# DRIVERS_CONNECTORS.net
KiCad netlist of a schematic drawn in Altium Designer
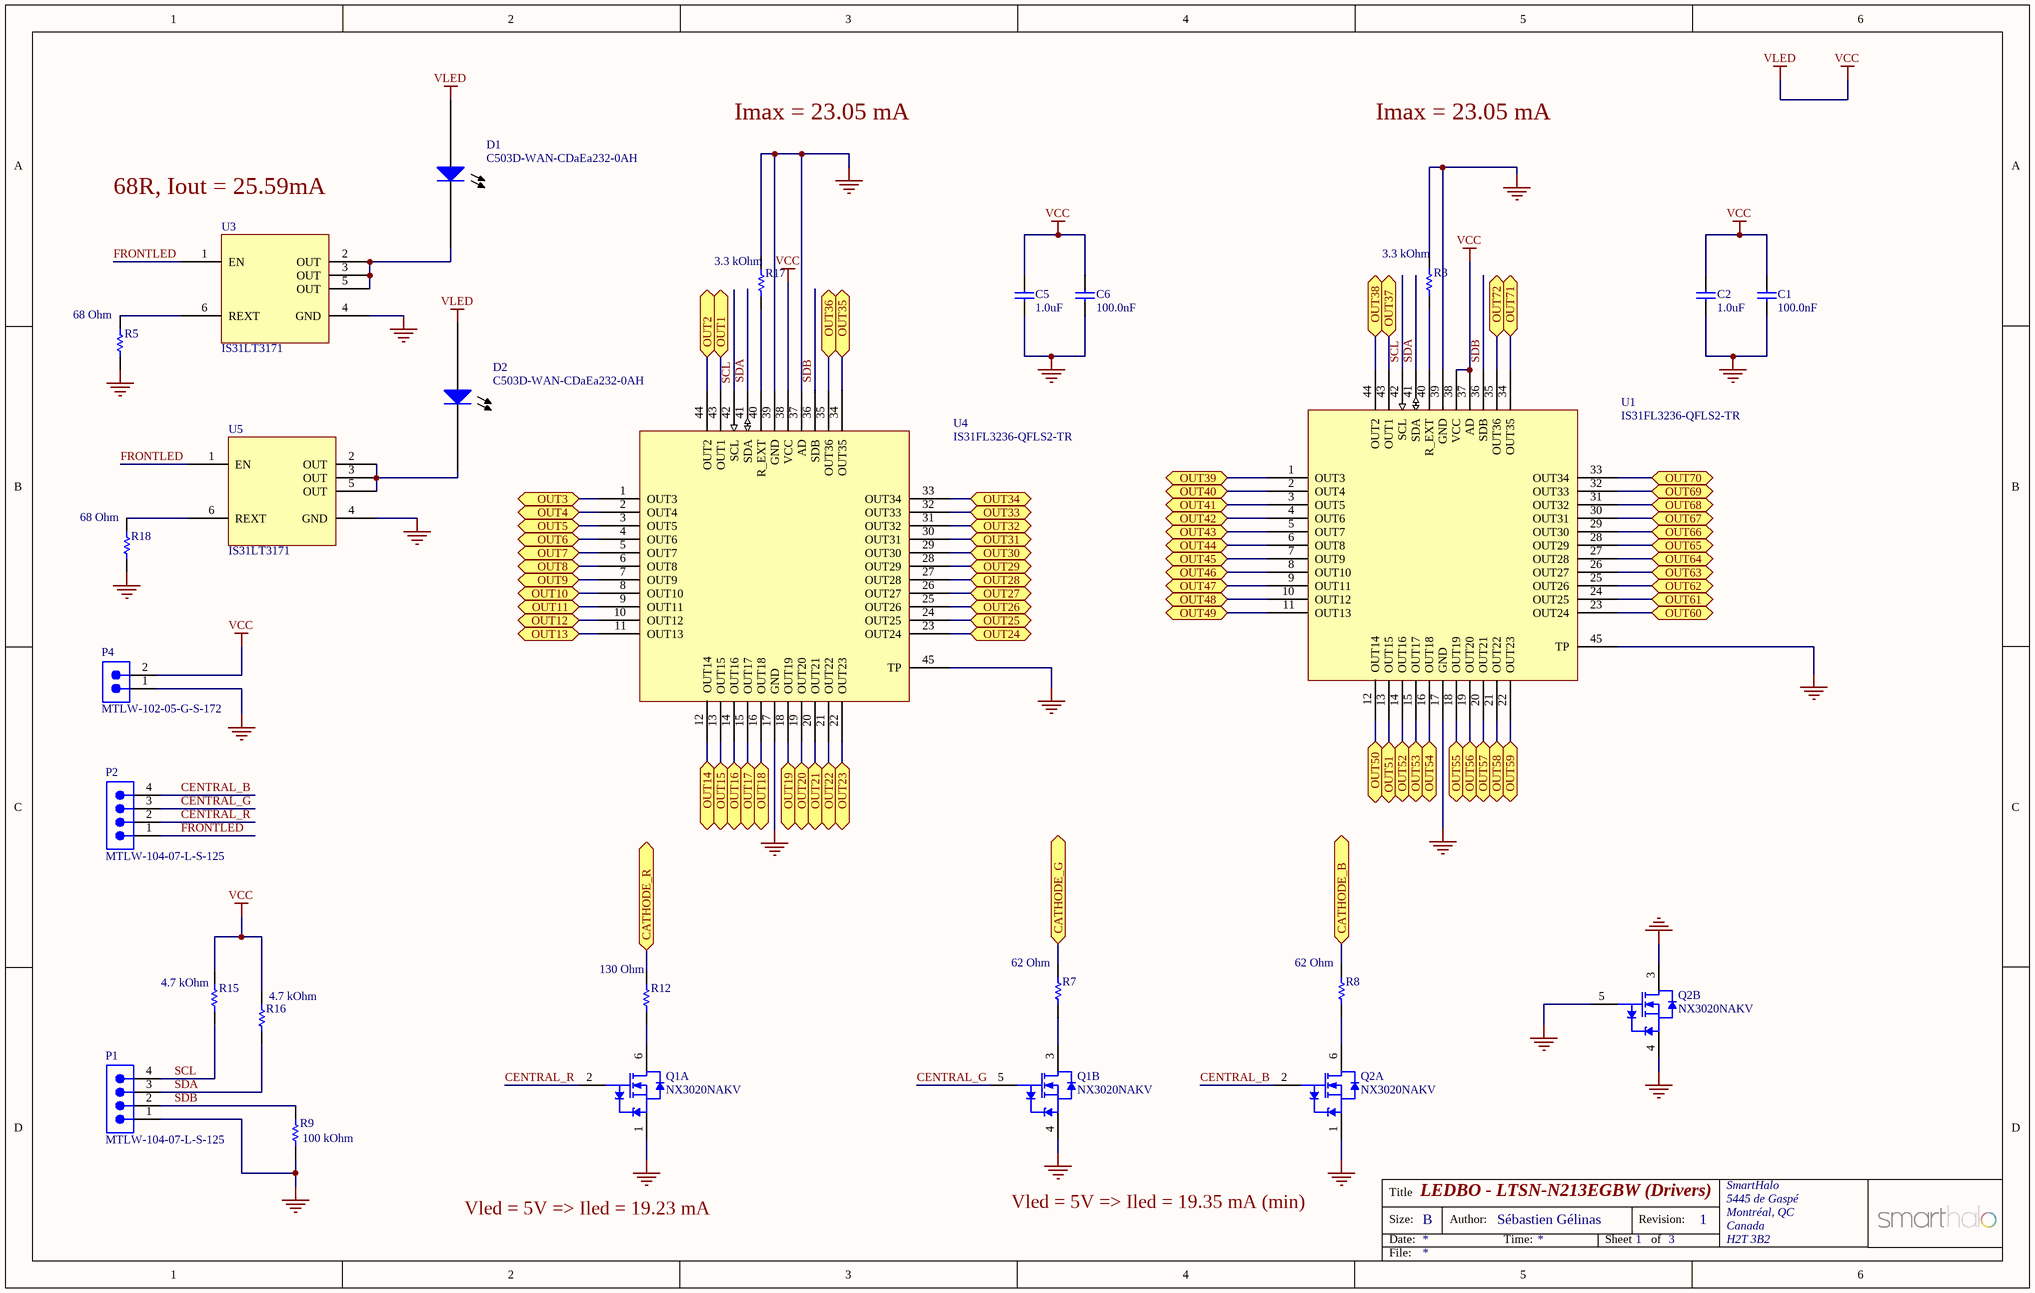
[diagram p0: DRIVERS_CONNECTORS.SchDoc]

(export (version "E")
  (design (tool "Eeschema 10.0.6"))
  (components
    (comp (ref "C1")
      (value "100.0nF")
      (footprint "CAPC0603(1608)100_N")
      (description "Chip Cap 0603 X7R 10%")
      (fields (field (name "PART NUMBER") "C0402-1n0") (field (name "PUBLISHER") "Nordic Semiconductor"))
      (libsource (lib "SmartHalo") (part "CAP0603"))
    )
    (comp (ref "C2")
      (value "1.0uF")
      (footprint "CAPC0603(1608)100_N")
      (description "Chip Cap 0603 X7R 10%")
      (fields (field (name "PART NUMBER") "C0402-1n0") (field (name "PUBLISHER") "Nordic Semiconductor"))
      (libsource (lib "SmartHalo") (part "CAP0603"))
    )
    (comp (ref "C5")
      (value "1.0uF")
      (footprint "CAPC0603(1608)100_N")
      (description "Chip Cap 0603 X7R 10%")
      (fields (field (name "PART NUMBER") "C0402-1n0") (field (name "PUBLISHER") "Nordic Semiconductor"))
      (libsource (lib "SmartHalo") (part "CAP0603"))
    )
    (comp (ref "C6")
      (value "100.0nF")
      (footprint "CAPC0603(1608)100_N")
      (description "Chip Cap 0603 X7R 10%")
      (fields (field (name "PART NUMBER") "C0402-1n0") (field (name "PUBLISHER") "Nordic Semiconductor"))
      (libsource (lib "SmartHalo") (part "CAP0603"))
    )
    (comp (ref "D1")
      (value "C503D-WAN-CDaEa232-0AH")
      (footprint "FRONTLED_PADS")
      (description "Cree 5mm Round LED C503D-WAN-CDaEa232-0AH")
      (fields (field (name "MANUFACTURER") "Cree"))
      (libsource (lib "SmartHalo") (part "C503D-WAN-CDaEa232-0AH"))
    )
    (comp (ref "D2")
      (value "C503D-WAN-CDaEa232-0AH")
      (footprint "FRONTLED_PADS")
      (description "Cree 5mm Round LED C503D-WAN-CDaEa232-0AH")
      (fields (field (name "MANUFACTURER") "Cree"))
      (libsource (lib "SmartHalo") (part "C503D-WAN-CDaEa232-0AH"))
    )
    (comp (ref "P1")
      (value "MTLW-104-07-L-S-125")
      (footprint "SMTC-MTLW-104-07-X-S-125")
      (fields (field (name "MANUFACTURER") "Samtec"))
      (libsource (lib "SmartHalo") (part "SMTC-MTLW-104-07-X-S-125"))
    )
    (comp (ref "P2")
      (value "MTLW-104-07-L-S-125")
      (footprint "SMTC-MTLW-104-07-X-S-125")
      (fields (field (name "MANUFACTURER") "Samtec"))
      (libsource (lib "SmartHalo") (part "SMTC-MTLW-104-07-X-S-125"))
    )
    (comp (ref "P4")
      (value "MTLW-102-05-G-S-172")
      (footprint "SMTC-MTLW-102-05-X-S-172")
      (fields (field (name "MANUFACTURER") "Samtec"))
      (libsource (lib "SmartHalo") (part "SMTC-MTLW-102-05-X-S-172"))
    )
    (comp (ref "Q1")
      (value "NX3020NAKV")
      (footprint "SOT666")
      (description "30 V, 200 mA dual N-channel Trench MOSFET")
      (fields (field (name "MANUFACTURER") "NXP Semiconductors"))
      (libsource (lib "SmartHalo") (part "NX3020NAKV"))
    )
    (comp (ref "Q2")
      (value "NX3020NAKV")
      (footprint "SOT666")
      (description "30 V, 200 mA dual N-channel Trench MOSFET")
      (fields (field (name "MANUFACTURER") "NXP Semiconductors"))
      (libsource (lib "SmartHalo") (part "NX3020NAKV"))
    )
    (comp (ref "R3")
      (value "3.3 kOhm")
      (footprint "RESC0603(1608)_M")
      (description "3K3 0.1W 5% 0603 (1608 Metric)  SMD")
      (fields (field (name "TOLERANCE") "5 %") (field (name "POWER") "0.1 W"))
      (libsource (lib "SmartHalo") (part "CMP-1012-00090-1"))
    )
    (comp (ref "R5")
      (value "68 Ohm")
      (footprint "RESC0603(1608)_M")
      (description "68R 0.1W 5% 0603 (1608 Metric)  SMD")
      (fields (field (name "TOLERANCE") "5 %") (field (name "POWER") "0.1 W"))
      (libsource (lib "SmartHalo") (part "CMP-1012-00090-1"))
    )
    (comp (ref "R7")
      (value "62 Ohm")
      (footprint "RESC0603(1608)_M")
      (description "62R 0.1W 5% 0603 (1608 Metric)  SMD")
      (fields (field (name "TOLERANCE") "5 %") (field (name "POWER") "0.1 W"))
      (libsource (lib "SmartHalo") (part "CMP-1012-00090-1"))
    )
    (comp (ref "R8")
      (value "62 Ohm")
      (footprint "RESC0603(1608)_M")
      (description "62R 0.1W 5% 0603 (1608 Metric)  SMD")
      (fields (field (name "TOLERANCE") "5 %") (field (name "POWER") "0.1 W"))
      (libsource (lib "SmartHalo") (part "CMP-1012-00090-1"))
    )
    (comp (ref "R9")
      (value "100 kOhm")
      (footprint "RESC0603(1608)_M")
      (description "100k 0.1W 5% 0603 (1608 Metric)  SMD")
      (fields (field (name "TOLERANCE") "5 %") (field (name "POWER") "0.1 W"))
      (libsource (lib "SmartHalo") (part "CMP-1012-00090-1"))
    )
    (comp (ref "R12")
      (value "130 Ohm")
      (footprint "RESC0603(1608)_M")
      (description "130R 0.1W 5% 0603 (1608 Metric)  SMD")
      (fields (field (name "TOLERANCE") "5 %") (field (name "POWER") "0.1 W"))
      (libsource (lib "SmartHalo") (part "CMP-1012-00090-1"))
    )
    (comp (ref "R15")
      (value "4.7 kOhm")
      (footprint "RESC0603(1608)_M")
      (description "4K7 0.1W 5% 0603 (1608 Metric)  SMD")
      (fields (field (name "TOLERANCE") "5 %") (field (name "POWER") "0.1 W"))
      (libsource (lib "SmartHalo") (part "CMP-1012-00090-1"))
    )
    (comp (ref "R16")
      (value "4.7 kOhm")
      (footprint "RESC0603(1608)_M")
      (description "4K7 0.1W 5% 0603 (1608 Metric)  SMD")
      (fields (field (name "TOLERANCE") "5 %") (field (name "POWER") "0.1 W"))
      (libsource (lib "SmartHalo") (part "CMP-1012-00090-1"))
    )
    (comp (ref "R17")
      (value "3.3 kOhm")
      (footprint "RESC0603(1608)_M")
      (description "3K3 0.1W 5% 0603 (1608 Metric)  SMD")
      (fields (field (name "TOLERANCE") "5 %") (field (name "POWER") "0.1 W"))
      (libsource (lib "SmartHalo") (part "CMP-1012-00090-1"))
    )
    (comp (ref "R18")
      (value "68 Ohm")
      (footprint "RESC0603(1608)_M")
      (description "68R 0.1W 5% 0603 (1608 Metric)  SMD")
      (fields (field (name "TOLERANCE") "5 %") (field (name "POWER") "0.1 W"))
      (libsource (lib "SmartHalo") (part "CMP-1012-00090-1"))
    )
    (comp (ref "U1")
      (value "IS31FL3236-QFLS2-TR")
      (footprint "QFN-44")
      (description "IC 36 CHANNELS LED DRIVER")
      (fields (field (name "MANUFACTURER") "ISSI"))
      (libsource (lib "SmartHalo") (part "IS31FL3236-QFLS2-TR"))
    )
    (comp (ref "U3")
      (value "IS31LT3171")
      (footprint "SOT23-6")
      (description "10-TO-150MA CONSTANT-CURRENT LED DRIVER")
      (libsource (lib "SmartHalo") (part "IS31LT3171"))
    )
    (comp (ref "U4")
      (value "IS31FL3236-QFLS2-TR")
      (footprint "QFN-44")
      (description "IC 36 CHANNELS LED DRIVER")
      (fields (field (name "MANUFACTURER") "ISSI"))
      (libsource (lib "SmartHalo") (part "IS31FL3236-QFLS2-TR"))
    )
    (comp (ref "U5")
      (value "IS31LT3171")
      (footprint "SOT23-6")
      (description "10-TO-150MA CONSTANT-CURRENT LED DRIVER")
      (libsource (lib "SmartHalo") (part "IS31LT3171"))
    )
  )
  (nets
    (net (code "1") (name "/CATHODE_B") (class "Default")
      (node (ref "R8") (pin "2") (pinfunction "2_2") (pintype "passive"))
    )
    (net (code "2") (name "/CATHODE_G") (class "Default")
      (node (ref "R7") (pin "2") (pinfunction "2_2") (pintype "passive"))
    )
    (net (code "3") (name "/CATHODE_R") (class "Default")
      (node (ref "R12") (pin "2") (pinfunction "2_2") (pintype "passive"))
    )
    (net (code "4") (name "/CENTRAL_B") (class "Default")
      (node (ref "P2") (pin "4") (pinfunction "4_4") (pintype "passive"))
      (node (ref "Q2") (pin "2") (pinfunction "G1_2") (pintype "passive"))
    )
    (net (code "5") (name "/CENTRAL_G") (class "Default")
      (node (ref "P2") (pin "3") (pinfunction "3_3") (pintype "passive"))
      (node (ref "Q1") (pin "5") (pinfunction "G2_5") (pintype "passive"))
    )
    (net (code "6") (name "/CENTRAL_R") (class "Default")
      (node (ref "P2") (pin "2") (pinfunction "2_2") (pintype "passive"))
      (node (ref "Q1") (pin "2") (pinfunction "G1_2") (pintype "passive"))
    )
    (net (code "7") (name "/FRONTLED") (class "Default")
      (node (ref "P2") (pin "1") (pinfunction "1_1") (pintype "passive"))
      (node (ref "U3") (pin "1") (pinfunction "EN_1") (pintype "passive"))
      (node (ref "U5") (pin "1") (pinfunction "EN_1") (pintype "passive"))
    )
    (net (code "8") (name "/OUT1") (class "Default")
      (node (ref "U4") (pin "43") (pinfunction "OUT1_43") (pintype "passive"))
    )
    (net (code "9") (name "/OUT2") (class "Default")
      (node (ref "U4") (pin "44") (pinfunction "OUT2_44") (pintype "passive"))
    )
    (net (code "10") (name "/OUT3") (class "Default")
      (node (ref "U4") (pin "1") (pinfunction "OUT3_1") (pintype "passive"))
    )
    (net (code "11") (name "/OUT4") (class "Default")
      (node (ref "U4") (pin "2") (pinfunction "OUT4_2") (pintype "passive"))
    )
    (net (code "12") (name "/OUT5") (class "Default")
      (node (ref "U4") (pin "3") (pinfunction "OUT5_3") (pintype "passive"))
    )
    (net (code "13") (name "/OUT6") (class "Default")
      (node (ref "U4") (pin "4") (pinfunction "OUT6_4") (pintype "passive"))
    )
    (net (code "14") (name "/OUT7") (class "Default")
      (node (ref "U4") (pin "5") (pinfunction "OUT7_5") (pintype "passive"))
    )
    (net (code "15") (name "/OUT8") (class "Default")
      (node (ref "U4") (pin "6") (pinfunction "OUT8_6") (pintype "passive"))
    )
    (net (code "16") (name "/OUT9") (class "Default")
      (node (ref "U4") (pin "7") (pinfunction "OUT9_7") (pintype "passive"))
    )
    (net (code "17") (name "/OUT10") (class "Default")
      (node (ref "U4") (pin "8") (pinfunction "OUT10_8") (pintype "passive"))
    )
    (net (code "18") (name "/OUT11") (class "Default")
      (node (ref "U4") (pin "9") (pinfunction "OUT11_9") (pintype "passive"))
    )
    (net (code "19") (name "/OUT12") (class "Default")
      (node (ref "U4") (pin "10") (pinfunction "OUT12_10") (pintype "passive"))
    )
    (net (code "20") (name "/OUT13") (class "Default")
      (node (ref "U4") (pin "11") (pinfunction "OUT13_11") (pintype "passive"))
    )
    (net (code "21") (name "/OUT14") (class "Default")
      (node (ref "U4") (pin "12") (pinfunction "OUT14_12") (pintype "passive"))
    )
    (net (code "22") (name "/OUT15") (class "Default")
      (node (ref "U4") (pin "13") (pinfunction "OUT15_13") (pintype "passive"))
    )
    (net (code "23") (name "/OUT16") (class "Default")
      (node (ref "U4") (pin "14") (pinfunction "OUT16_14") (pintype "passive"))
    )
    (net (code "24") (name "/OUT17") (class "Default")
      (node (ref "U4") (pin "15") (pinfunction "OUT17_15") (pintype "passive"))
    )
    (net (code "25") (name "/OUT18") (class "Default")
      (node (ref "U4") (pin "16") (pinfunction "OUT18_16") (pintype "passive"))
    )
    (net (code "26") (name "/OUT19") (class "Default")
      (node (ref "U4") (pin "18") (pinfunction "OUT19_18") (pintype "passive"))
    )
    (net (code "27") (name "/OUT20") (class "Default")
      (node (ref "U4") (pin "19") (pinfunction "OUT20_19") (pintype "passive"))
    )
    (net (code "28") (name "/OUT21") (class "Default")
      (node (ref "U4") (pin "20") (pinfunction "OUT21_20") (pintype "passive"))
    )
    (net (code "29") (name "/OUT22") (class "Default")
      (node (ref "U4") (pin "21") (pinfunction "OUT22_21") (pintype "passive"))
    )
    (net (code "30") (name "/OUT23") (class "Default")
      (node (ref "U4") (pin "22") (pinfunction "OUT23_22") (pintype "passive"))
    )
    (net (code "31") (name "/OUT24") (class "Default")
      (node (ref "U4") (pin "23") (pinfunction "OUT24_23") (pintype "passive"))
    )
    (net (code "32") (name "/OUT25") (class "Default")
      (node (ref "U4") (pin "24") (pinfunction "OUT25_24") (pintype "passive"))
    )
    (net (code "33") (name "/OUT26") (class "Default")
      (node (ref "U4") (pin "25") (pinfunction "OUT26_25") (pintype "passive"))
    )
    (net (code "34") (name "/OUT27") (class "Default")
      (node (ref "U4") (pin "26") (pinfunction "OUT27_26") (pintype "passive"))
    )
    (net (code "35") (name "/OUT28") (class "Default")
      (node (ref "U4") (pin "27") (pinfunction "OUT28_27") (pintype "passive"))
    )
    (net (code "36") (name "/OUT29") (class "Default")
      (node (ref "U4") (pin "28") (pinfunction "OUT29_28") (pintype "passive"))
    )
    (net (code "37") (name "/OUT30") (class "Default")
      (node (ref "U4") (pin "29") (pinfunction "OUT30_29") (pintype "passive"))
    )
    (net (code "38") (name "/OUT31") (class "Default")
      (node (ref "U4") (pin "30") (pinfunction "OUT31_30") (pintype "passive"))
    )
    (net (code "39") (name "/OUT32") (class "Default")
      (node (ref "U4") (pin "31") (pinfunction "OUT32_31") (pintype "passive"))
    )
    (net (code "40") (name "/OUT33") (class "Default")
      (node (ref "U4") (pin "32") (pinfunction "OUT33_32") (pintype "passive"))
    )
    (net (code "41") (name "/OUT34") (class "Default")
      (node (ref "U4") (pin "33") (pinfunction "OUT34_33") (pintype "passive"))
    )
    (net (code "42") (name "/OUT35") (class "Default")
      (node (ref "U4") (pin "34") (pinfunction "OUT35_34") (pintype "passive"))
    )
    (net (code "43") (name "/OUT36") (class "Default")
      (node (ref "U4") (pin "35") (pinfunction "OUT36_35") (pintype "passive"))
    )
    (net (code "44") (name "/OUT37") (class "Default")
      (node (ref "U1") (pin "43") (pinfunction "OUT1_43") (pintype "passive"))
    )
    (net (code "45") (name "/OUT38") (class "Default")
      (node (ref "U1") (pin "44") (pinfunction "OUT2_44") (pintype "passive"))
    )
    (net (code "46") (name "/OUT39") (class "Default")
      (node (ref "U1") (pin "1") (pinfunction "OUT3_1") (pintype "passive"))
    )
    (net (code "47") (name "/OUT40") (class "Default")
      (node (ref "U1") (pin "2") (pinfunction "OUT4_2") (pintype "passive"))
    )
    (net (code "48") (name "/OUT41") (class "Default")
      (node (ref "U1") (pin "3") (pinfunction "OUT5_3") (pintype "passive"))
    )
    (net (code "49") (name "/OUT42") (class "Default")
      (node (ref "U1") (pin "4") (pinfunction "OUT6_4") (pintype "passive"))
    )
    (net (code "50") (name "/OUT43") (class "Default")
      (node (ref "U1") (pin "5") (pinfunction "OUT7_5") (pintype "passive"))
    )
    (net (code "51") (name "/OUT44") (class "Default")
      (node (ref "U1") (pin "6") (pinfunction "OUT8_6") (pintype "passive"))
    )
    (net (code "52") (name "/OUT45") (class "Default")
      (node (ref "U1") (pin "7") (pinfunction "OUT9_7") (pintype "passive"))
    )
    (net (code "53") (name "/OUT46") (class "Default")
      (node (ref "U1") (pin "8") (pinfunction "OUT10_8") (pintype "passive"))
    )
    (net (code "54") (name "/OUT47") (class "Default")
      (node (ref "U1") (pin "9") (pinfunction "OUT11_9") (pintype "passive"))
    )
    (net (code "55") (name "/OUT48") (class "Default")
      (node (ref "U1") (pin "10") (pinfunction "OUT12_10") (pintype "passive"))
    )
    (net (code "56") (name "/OUT49") (class "Default")
      (node (ref "U1") (pin "11") (pinfunction "OUT13_11") (pintype "passive"))
    )
    (net (code "57") (name "/OUT50") (class "Default")
      (node (ref "U1") (pin "12") (pinfunction "OUT14_12") (pintype "passive"))
    )
    (net (code "58") (name "/OUT51") (class "Default")
      (node (ref "U1") (pin "13") (pinfunction "OUT15_13") (pintype "passive"))
    )
    (net (code "59") (name "/OUT52") (class "Default")
      (node (ref "U1") (pin "14") (pinfunction "OUT16_14") (pintype "passive"))
    )
    (net (code "60") (name "/OUT53") (class "Default")
      (node (ref "U1") (pin "15") (pinfunction "OUT17_15") (pintype "passive"))
    )
    (net (code "61") (name "/OUT54") (class "Default")
      (node (ref "U1") (pin "16") (pinfunction "OUT18_16") (pintype "passive"))
    )
    (net (code "62") (name "/OUT55") (class "Default")
      (node (ref "U1") (pin "18") (pinfunction "OUT19_18") (pintype "passive"))
    )
    (net (code "63") (name "/OUT56") (class "Default")
      (node (ref "U1") (pin "19") (pinfunction "OUT20_19") (pintype "passive"))
    )
    (net (code "64") (name "/OUT57") (class "Default")
      (node (ref "U1") (pin "20") (pinfunction "OUT21_20") (pintype "passive"))
    )
    (net (code "65") (name "/OUT58") (class "Default")
      (node (ref "U1") (pin "21") (pinfunction "OUT22_21") (pintype "passive"))
    )
    (net (code "66") (name "/OUT59") (class "Default")
      (node (ref "U1") (pin "22") (pinfunction "OUT23_22") (pintype "passive"))
    )
    (net (code "67") (name "/OUT60") (class "Default")
      (node (ref "U1") (pin "23") (pinfunction "OUT24_23") (pintype "passive"))
    )
    (net (code "68") (name "/OUT61") (class "Default")
      (node (ref "U1") (pin "24") (pinfunction "OUT25_24") (pintype "passive"))
    )
    (net (code "69") (name "/OUT62") (class "Default")
      (node (ref "U1") (pin "25") (pinfunction "OUT26_25") (pintype "passive"))
    )
    (net (code "70") (name "/OUT63") (class "Default")
      (node (ref "U1") (pin "26") (pinfunction "OUT27_26") (pintype "passive"))
    )
    (net (code "71") (name "/OUT64") (class "Default")
      (node (ref "U1") (pin "27") (pinfunction "OUT28_27") (pintype "passive"))
    )
    (net (code "72") (name "/OUT65") (class "Default")
      (node (ref "U1") (pin "28") (pinfunction "OUT29_28") (pintype "passive"))
    )
    (net (code "73") (name "/OUT66") (class "Default")
      (node (ref "U1") (pin "29") (pinfunction "OUT30_29") (pintype "passive"))
    )
    (net (code "74") (name "/OUT67") (class "Default")
      (node (ref "U1") (pin "30") (pinfunction "OUT31_30") (pintype "passive"))
    )
    (net (code "75") (name "/OUT68") (class "Default")
      (node (ref "U1") (pin "31") (pinfunction "OUT32_31") (pintype "passive"))
    )
    (net (code "76") (name "/OUT69") (class "Default")
      (node (ref "U1") (pin "32") (pinfunction "OUT33_32") (pintype "passive"))
    )
    (net (code "77") (name "/OUT70") (class "Default")
      (node (ref "U1") (pin "33") (pinfunction "OUT34_33") (pintype "passive"))
    )
    (net (code "78") (name "/OUT71") (class "Default")
      (node (ref "U1") (pin "34") (pinfunction "OUT35_34") (pintype "passive"))
    )
    (net (code "79") (name "/OUT72") (class "Default")
      (node (ref "U1") (pin "35") (pinfunction "OUT36_35") (pintype "passive"))
    )
    (net (code "80") (name "/SCL") (class "Default")
      (node (ref "P1") (pin "4") (pinfunction "4_4") (pintype "passive"))
      (node (ref "R15") (pin "1") (pinfunction "1_1") (pintype "passive"))
      (node (ref "U1") (pin "42") (pinfunction "SCL_42") (pintype "input"))
      (node (ref "U4") (pin "42") (pinfunction "SCL_42") (pintype "input"))
    )
    (net (code "81") (name "/SDA") (class "Default")
      (node (ref "P1") (pin "3") (pinfunction "3_3") (pintype "passive"))
      (node (ref "R16") (pin "1") (pinfunction "1_1") (pintype "passive"))
      (node (ref "U1") (pin "41") (pinfunction "SDA_41") (pintype "bidirectional"))
      (node (ref "U4") (pin "41") (pinfunction "SDA_41") (pintype "bidirectional"))
    )
    (net (code "82") (name "/SDB") (class "Default")
      (node (ref "P1") (pin "2") (pinfunction "2_2") (pintype "passive"))
      (node (ref "R9") (pin "2") (pinfunction "2_2") (pintype "passive"))
      (node (ref "U1") (pin "36") (pinfunction "SDB_36") (pintype "passive"))
      (node (ref "U4") (pin "36") (pinfunction "SDB_36") (pintype "passive"))
    )
    (net (code "83") (name "GND") (class "Default")
      (node (ref "C1") (pin "2") (pinfunction "2_2") (pintype "passive"))
      (node (ref "C2") (pin "2") (pinfunction "2_2") (pintype "passive"))
      (node (ref "C5") (pin "2") (pinfunction "2_2") (pintype "passive"))
      (node (ref "C6") (pin "2") (pinfunction "2_2") (pintype "passive"))
      (node (ref "P1") (pin "1") (pinfunction "1_1") (pintype "passive"))
      (node (ref "P4") (pin "1") (pinfunction "1_1") (pintype "passive"))
      (node (ref "Q1") (pin "1") (pinfunction "S1_1") (pintype "passive"))
      (node (ref "Q1") (pin "4") (pinfunction "S2_4") (pintype "passive"))
      (node (ref "Q2") (pin "1") (pinfunction "S1_1") (pintype "passive"))
      (node (ref "Q2") (pin "3") (pinfunction "D2_3") (pintype "passive"))
      (node (ref "Q2") (pin "4") (pinfunction "S2_4") (pintype "passive"))
      (node (ref "Q2") (pin "5") (pinfunction "G2_5") (pintype "passive"))
      (node (ref "R17") (pin "2") (pinfunction "2_2") (pintype "passive"))
      (node (ref "R18") (pin "1") (pinfunction "1_1") (pintype "passive"))
      (node (ref "R3") (pin "2") (pinfunction "2_2") (pintype "passive"))
      (node (ref "R5") (pin "1") (pinfunction "1_1") (pintype "passive"))
      (node (ref "R9") (pin "1") (pinfunction "1_1") (pintype "passive"))
      (node (ref "U1") (pin "17") (pinfunction "GND_17") (pintype "power_in"))
      (node (ref "U1") (pin "39") (pinfunction "GND_39") (pintype "power_in"))
      (node (ref "U1") (pin "45") (pinfunction "TP_45") (pintype "power_in"))
      (node (ref "U3") (pin "4") (pinfunction "GND_4") (pintype "passive"))
      (node (ref "U4") (pin "17") (pinfunction "GND_17") (pintype "power_in"))
      (node (ref "U4") (pin "37") (pinfunction "AD_37") (pintype "passive"))
      (node (ref "U4") (pin "39") (pinfunction "GND_39") (pintype "power_in"))
      (node (ref "U4") (pin "45") (pinfunction "TP_45") (pintype "power_in"))
      (node (ref "U5") (pin "4") (pinfunction "GND_4") (pintype "passive"))
    )
    (net (code "84") (name "Net-(D1-Cathode)") (class "Default")
      (node (ref "D1") (pin "2") (pinfunction "Cathode_2") (pintype "passive"))
      (node (ref "U3") (pin "2") (pinfunction "OUT_2") (pintype "passive"))
      (node (ref "U3") (pin "3") (pinfunction "OUT_3") (pintype "passive"))
      (node (ref "U3") (pin "5") (pinfunction "OUT_5") (pintype "passive"))
    )
    (net (code "85") (name "Net-(D2-Cathode)") (class "Default")
      (node (ref "D2") (pin "2") (pinfunction "Cathode_2") (pintype "passive"))
      (node (ref "U5") (pin "2") (pinfunction "OUT_2") (pintype "passive"))
      (node (ref "U5") (pin "3") (pinfunction "OUT_3") (pintype "passive"))
      (node (ref "U5") (pin "5") (pinfunction "OUT_5") (pintype "passive"))
    )
    (net (code "86") (name "Net-(Q1A-D1)") (class "Default")
      (node (ref "Q1") (pin "6") (pinfunction "D1_6") (pintype "passive"))
      (node (ref "R12") (pin "1") (pinfunction "1_1") (pintype "passive"))
    )
    (net (code "87") (name "Net-(Q1B-D2)") (class "Default")
      (node (ref "Q1") (pin "3") (pinfunction "D2_3") (pintype "passive"))
      (node (ref "R7") (pin "1") (pinfunction "1_1") (pintype "passive"))
    )
    (net (code "88") (name "Net-(Q2A-D1)") (class "Default")
      (node (ref "Q2") (pin "6") (pinfunction "D1_6") (pintype "passive"))
      (node (ref "R8") (pin "1") (pinfunction "1_1") (pintype "passive"))
    )
    (net (code "89") (name "Net-(U1-R_EXT)") (class "Default")
      (node (ref "R3") (pin "1") (pinfunction "1_1") (pintype "passive"))
      (node (ref "U1") (pin "40") (pinfunction "R_EXT_40") (pintype "passive"))
    )
    (net (code "90") (name "Net-(U3-REXT)") (class "Default")
      (node (ref "R5") (pin "2") (pinfunction "2_2") (pintype "passive"))
      (node (ref "U3") (pin "6") (pinfunction "REXT_6") (pintype "passive"))
    )
    (net (code "91") (name "Net-(U4-R_EXT)") (class "Default")
      (node (ref "R17") (pin "1") (pinfunction "1_1") (pintype "passive"))
      (node (ref "U4") (pin "40") (pinfunction "R_EXT_40") (pintype "passive"))
    )
    (net (code "92") (name "Net-(U5-REXT)") (class "Default")
      (node (ref "R18") (pin "2") (pinfunction "2_2") (pintype "passive"))
      (node (ref "U5") (pin "6") (pinfunction "REXT_6") (pintype "passive"))
    )
    (net (code "93") (name "VCC") (class "Default")
      (node (ref "C1") (pin "1") (pinfunction "1_1") (pintype "passive"))
      (node (ref "C2") (pin "1") (pinfunction "1_1") (pintype "passive"))
      (node (ref "C5") (pin "1") (pinfunction "1_1") (pintype "passive"))
      (node (ref "C6") (pin "1") (pinfunction "1_1") (pintype "passive"))
      (node (ref "D1") (pin "1") (pinfunction "Anode_1") (pintype "passive"))
      (node (ref "D2") (pin "1") (pinfunction "Anode_1") (pintype "passive"))
      (node (ref "P4") (pin "2") (pinfunction "2_2") (pintype "passive"))
      (node (ref "R15") (pin "2") (pinfunction "2_2") (pintype "passive"))
      (node (ref "R16") (pin "2") (pinfunction "2_2") (pintype "passive"))
      (node (ref "U1") (pin "37") (pinfunction "AD_37") (pintype "passive"))
      (node (ref "U1") (pin "38") (pinfunction "VCC_38") (pintype "power_in"))
      (node (ref "U4") (pin "38") (pinfunction "VCC_38") (pintype "power_in"))
    )
  )
)
